# Suiveur.net
KiCad netlist of a schematic drawn in Altium Designer
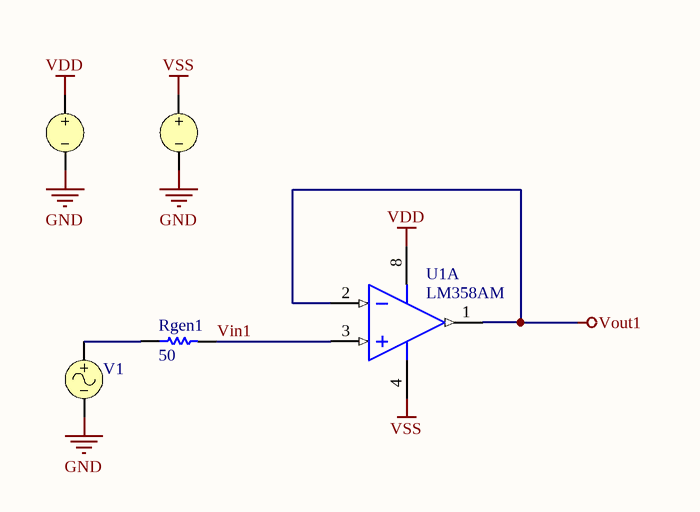
[diagram p0: Suiveur.SchDoc]

(export (version "E")
  (design (tool "Eeschema 10.0.6"))
  (components
    (comp (ref "Rgen1")
      (value "50")
      (description "Resistor")
      (libsource (lib "Simulation Generic Components") (part "Resistor"))
    )
    (comp (ref "U1")
      (value "LM358AM")
      (footprint "M08A_N")
      (description "Low Power Dual Operational Amplifier, 8-pin Narrow SOIC")
      (fields
        (field (name "MANUFACTURER") "National Semiconductor")
        (field (name "PUBLISHER") "Altium Limited")
      )
      (libsource (lib "NSC Amplifier") (part "LM358AM"))
    )
    (comp (ref "V+")
      (value "DC 5")
      (description "Voltage Source")
      (fields (field (name "PUBLISHER") "Altium Limited"))
      (libsource (lib "Simulation Sources") (part "VSRC"))
    )
    (comp (ref "V-")
      (value "DC -5")
      (description "Voltage Source")
      (fields (field (name "PUBLISHER") "Altium Limited"))
      (libsource (lib "Simulation Sources") (part "VSRC"))
    )
    (comp (ref "V1")
      (value "SIN(0 1 10k 0 0 0)")
      (description "Sinusoidal Voltage Source")
      (fields (field (name "PUBLISHER") "Altium Limited"))
      (libsource (lib "Simulation Sources") (part "VSIN"))
    )
  )
  (nets
    (net (code "1") (name "/Vin1") (class "Default")
      (node (ref "Rgen1") (pin "2") (pinfunction "2_2") (pintype "passive"))
      (node (ref "U1") (pin "3") (pinfunction "INA+_3") (pintype "input"))
    )
    (net (code "2") (name "GND") (class "Default")
      (node (ref "V+") (pin "2") (pinfunction "2_2") (pintype "passive"))
      (node (ref "V-") (pin "2") (pinfunction "2_2") (pintype "passive"))
      (node (ref "V1") (pin "2") (pinfunction "2_2") (pintype "passive"))
    )
    (net (code "3") (name "Net-(Rgen1-Pad1)") (class "Default")
      (node (ref "Rgen1") (pin "1") (pinfunction "1_1") (pintype "passive"))
      (node (ref "V1") (pin "1") (pinfunction "1_1") (pintype "passive"))
    )
    (net (code "4") (name "VDD") (class "Default")
      (node (ref "U1") (pin "8") (pinfunction "V+_8") (pintype "power_in"))
      (node (ref "V+") (pin "1") (pinfunction "1_1") (pintype "passive"))
    )
    (net (code "5") (name "VSS") (class "Default")
      (node (ref "U1") (pin "4") (pinfunction "GND_4") (pintype "power_in"))
      (node (ref "V-") (pin "1") (pinfunction "1_1") (pintype "passive"))
    )
    (net (code "6") (name "Vout1") (class "Default")
      (node (ref "U1") (pin "1") (pinfunction "OUTA_1") (pintype "output"))
      (node (ref "U1") (pin "2") (pinfunction "INA-_2") (pintype "input"))
    )
  )
)
